# GSM_Power.net
KiCad netlist of a schematic drawn in Altium Designer
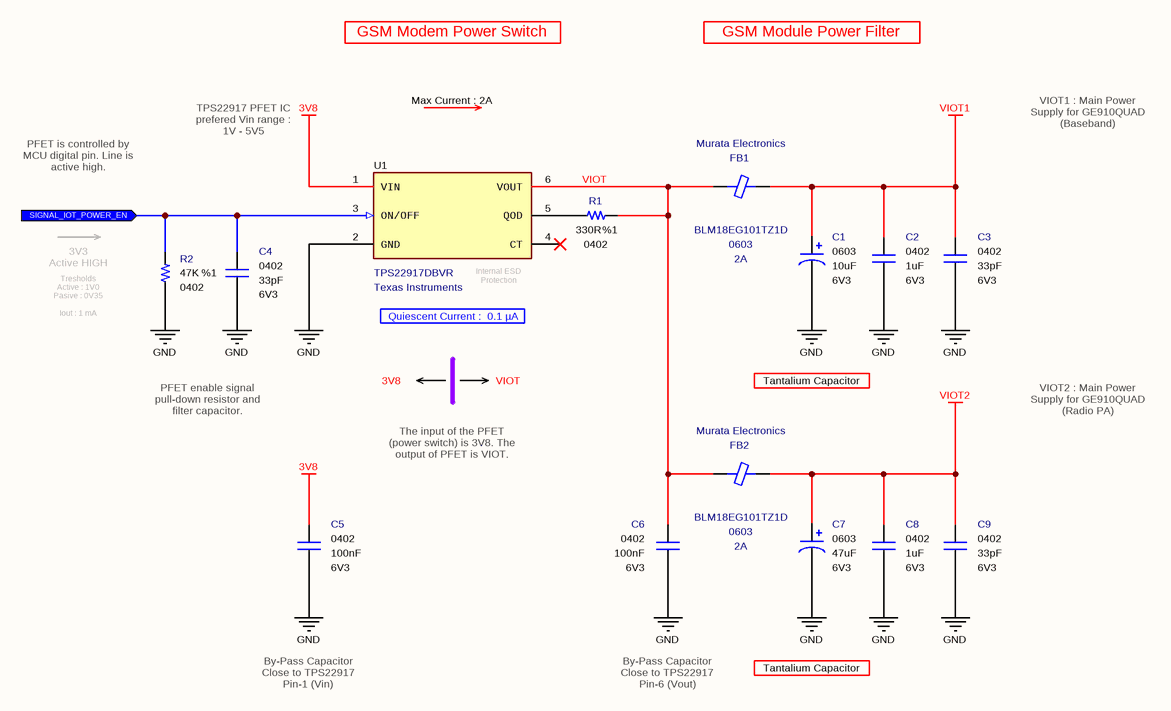
[diagram p0: GSM Power.SchDoc]

(export (version "E")
  (design (tool "Eeschema 10.0.6"))
  (components
    (comp (ref "C1")
      (value "10uF")
      (footprint "CAPACITOR_0603 - TANTALUM")
      (description "Capacitor - 10uF [0603] (Tantalium)")
      (fields
        (field (name "TOLERANCE") "20%")
        (field (name "CASE") "0603")
        (field (name "VOLTAGE") "6V3")
        (field (name "MANUFACTURER PART NUMBER") "F380J106MMAAH3")
      )
      (libsource (lib "Ovoo_Library") (part "Capacitor - 10uF [0603-6V3] (Tantalium)"))
    )
    (comp (ref "C2")
      (value "1uF")
      (footprint "CAPACITOR_0402")
      (description "Capacitor - 1uF [0402] (Ceramic)")
      (fields
        (field (name "TOLERANCE") "20%")
        (field (name "CASE") "0402")
        (field (name "VOLTAGE") "6V3")
        (field (name "MANUFACTURER PART NUMBER") "GRM153R60J105ME95D")
      )
      (libsource (lib "Ovoo_Library") (part "Capacitor - 1uF [0402-6V3]"))
    )
    (comp (ref "C3")
      (value "33pF")
      (footprint "CAPACITOR_0402")
      (description "Capacitor - 33pF [0402] (Ceramic)")
      (fields
        (field (name "TOLERANCE") "10%")
        (field (name "CASE") "0402")
        (field (name "VOLTAGE") "6V3")
        (field (name "MANUFACTURER PART NUMBER") "C0402C330J9RACAUTO")
      )
      (libsource (lib "Ovoo_Library") (part "Capacitor - 33pF [0402-6V3]"))
    )
    (comp (ref "C4")
      (value "33pF")
      (footprint "CAPACITOR_0402")
      (description "Capacitor - 33pF [0402] (Ceramic)")
      (fields
        (field (name "TOLERANCE") "10%")
        (field (name "CASE") "0402")
        (field (name "VOLTAGE") "6V3")
        (field (name "MANUFACTURER PART NUMBER") "C0402C330J9RACAUTO")
      )
      (libsource (lib "Ovoo_Library") (part "Capacitor - 33pF [0402-6V3]"))
    )
    (comp (ref "C5")
      (value "100nF")
      (footprint "CAPACITOR_0402")
      (description "Capacitor - 100nF [0402-6V3] (Ceramic)")
      (fields
        (field (name "CASE") "0402")
        (field (name "TOLERANCE") "%10")
        (field (name "VOLTAGE") "6V3")
        (field (name "MANUFACTURER PART NUMBER") "04026D104KAT4A")
      )
      (libsource (lib "Ovoo_Library") (part "Capacitor - 100nF [0402-6V3]"))
    )
    (comp (ref "C6")
      (value "100nF")
      (footprint "CAPACITOR_0402")
      (description "Capacitor - 100nF [0402-6V3] (Ceramic)")
      (fields
        (field (name "CASE") "0402")
        (field (name "TOLERANCE") "%10")
        (field (name "VOLTAGE") "6V3")
        (field (name "MANUFACTURER PART NUMBER") "04026D104KAT4A")
      )
      (libsource (lib "Ovoo_Library") (part "Capacitor - 100nF [0402-6V3]"))
    )
    (comp (ref "C7")
      (value "47uF")
      (footprint "CAPACITOR_0603 - TANTALUM")
      (description "Capacitor - 47uF [0603] (Tantalium)")
      (fields
        (field (name "TOLERANCE") "20%")
        (field (name "CASE") "0603")
        (field (name "VOLTAGE") "6V3")
        (field (name "MANUFACTURER PART NUMBER") "F380J476MMAAXEH3")
      )
      (libsource (lib "Ovoo_Library") (part "Capacitor - 47u [0603-6V3] (Tantalium)"))
    )
    (comp (ref "C8")
      (value "1uF")
      (footprint "CAPACITOR_0402")
      (description "Capacitor - 1uF [0402] (Ceramic)")
      (fields
        (field (name "TOLERANCE") "20%")
        (field (name "CASE") "0402")
        (field (name "VOLTAGE") "6V3")
        (field (name "MANUFACTURER PART NUMBER") "GRM153R60J105ME95D")
      )
      (libsource (lib "Ovoo_Library") (part "Capacitor - 1uF [0402-6V3]"))
    )
    (comp (ref "C9")
      (value "33pF")
      (footprint "CAPACITOR_0402")
      (description "Capacitor - 33pF [0402] (Ceramic)")
      (fields
        (field (name "TOLERANCE") "10%")
        (field (name "CASE") "0402")
        (field (name "VOLTAGE") "6V3")
        (field (name "MANUFACTURER PART NUMBER") "C0402C330J9RACAUTO")
      )
      (libsource (lib "Ovoo_Library") (part "Capacitor - 33pF [0402-6V3]"))
    )
    (comp (ref "FB1")
      (value "BLM18EG101TZ1D")
      (footprint "INDUCATOR_0603")
      (description "Ferrite Beads 0603 100ohms 2000mA Auto Infotainment")
      (fields
        (field (name "TOLERANCE") "25%")
        (field (name "CASE") "0603")
        (field (name "MAXIMUM DC CURRENT") "2A")
        (field (name "MOUSER PART NUMBER") "81-BLM18EG101TZ1D")
        (field (name "MANUFACTURER NAME") "Murata Electronics")
      )
      (libsource (lib "Ovoo_Library") (part "Ferrite Bead - 2A [0603]"))
    )
    (comp (ref "FB2")
      (value "BLM18EG101TZ1D")
      (footprint "INDUCATOR_0603")
      (description "Ferrite Beads 0603 100ohms 2000mA Auto Infotainment")
      (fields
        (field (name "TOLERANCE") "25%")
        (field (name "CASE") "0603")
        (field (name "MAXIMUM DC CURRENT") "2A")
        (field (name "MOUSER PART NUMBER") "81-BLM18EG101TZ1D")
        (field (name "MANUFACTURER NAME") "Murata Electronics")
      )
      (libsource (lib "Ovoo_Library") (part "Ferrite Bead - 2A [0603]"))
    )
    (comp (ref "R1")
      (value "330R")
      (footprint "RESISTOR_0402")
      (description "Thick Film Resistors - SMD 1/16 W 330 Ohm 1%")
      (fields
        (field (name "TOLERANCE") "%1")
        (field (name "CASE") "0402")
        (field (name "MANUFACTURER PART NUMBER") "CRCW0402330RFKED")
        (field (name "MOUSER PART NUMBER") "71-CRCW0402-330-E3")
      )
      (libsource (lib "Ovoo_Library") (part "Resistor - 330R"))
    )
    (comp (ref "R2")
      (value "47K")
      (footprint "RESISTOR_0402")
      (description "Thick Film Resistors - SMD 1/16 W 47 Kohms 1%")
      (fields
        (field (name "TOLERANCE") "%1")
        (field (name "CASE") "0402")
        (field (name "MANUFACTURER PART NUMBER") "CRCW040247K0FKED")
        (field (name "Comment") "47K - 0402 - %1 - 1/16W")
      )
      (libsource (lib "Ovoo_Library") (part "Resistor - 47K"))
    )
    (comp (ref "U1")
      (value "Power Switch")
      (footprint "SOT-23-6")
      (description "Power Switch MosFet")
      (fields
        (field (name "MOUSER PART NUMBER") "595-TPS22917DBVR")
        (field (name "MANUFACTURER PART NUMBER") "TPS22917DBVR")
        (field (name "MANUFACTURER NAME") "Texas Instruments")
      )
      (libsource (lib "Ovoo_Library") (part "IC - TPS22917DBVR"))
    )
  )
  (nets
    (net (code "1") (name "/SIGNAL_IOT_POWER_EN") (class "Default")
      (node (ref "C4") (pin "2") (pinfunction "2_2") (pintype "passive"))
      (node (ref "R2") (pin "2") (pinfunction "2_2") (pintype "passive"))
      (node (ref "U1") (pin "3") (pinfunction "ON/OFF_3") (pintype "input"))
    )
    (net (code "2") (name "/VIOT") (class "Default")
      (node (ref "C6") (pin "1") (pinfunction "1_1") (pintype "passive"))
      (node (ref "FB1") (pin "1") (pinfunction "1_1") (pintype "passive"))
      (node (ref "FB2") (pin "1") (pinfunction "1_1") (pintype "passive"))
      (node (ref "R1") (pin "1") (pinfunction "1_1") (pintype "passive"))
      (node (ref "U1") (pin "6") (pinfunction "VOUT_6") (pintype "power_in"))
    )
    (net (code "3") (name "3V8") (class "Default")
      (node (ref "C5") (pin "1") (pinfunction "1_1") (pintype "passive"))
      (node (ref "U1") (pin "1") (pinfunction "VIN_1") (pintype "power_in"))
    )
    (net (code "4") (name "GND") (class "Default")
      (node (ref "C1") (pin "2") (pinfunction "2_2") (pintype "passive"))
      (node (ref "C2") (pin "1") (pinfunction "1_1") (pintype "passive"))
      (node (ref "C3") (pin "1") (pinfunction "1_1") (pintype "passive"))
      (node (ref "C4") (pin "1") (pinfunction "1_1") (pintype "passive"))
      (node (ref "C5") (pin "2") (pinfunction "2_2") (pintype "passive"))
      (node (ref "C6") (pin "2") (pinfunction "2_2") (pintype "passive"))
      (node (ref "C7") (pin "2") (pinfunction "2_2") (pintype "passive"))
      (node (ref "C8") (pin "1") (pinfunction "1_1") (pintype "passive"))
      (node (ref "C9") (pin "1") (pinfunction "1_1") (pintype "passive"))
      (node (ref "R2") (pin "1") (pinfunction "1_1") (pintype "passive"))
      (node (ref "U1") (pin "2") (pinfunction "GND_2") (pintype "power_in"))
    )
    (net (code "5") (name "Net-(U1-QOD)") (class "Default")
      (node (ref "R1") (pin "2") (pinfunction "2_2") (pintype "passive"))
      (node (ref "U1") (pin "5") (pinfunction "QOD_5") (pintype "power_in"))
    )
    (net (code "6") (name "VIOT1") (class "Default")
      (node (ref "C1") (pin "1") (pinfunction "1_1") (pintype "passive"))
      (node (ref "C2") (pin "2") (pinfunction "2_2") (pintype "passive"))
      (node (ref "C3") (pin "2") (pinfunction "2_2") (pintype "passive"))
      (node (ref "FB1") (pin "2") (pinfunction "2_2") (pintype "passive"))
    )
    (net (code "7") (name "VIOT2") (class "Default")
      (node (ref "C7") (pin "1") (pinfunction "1_1") (pintype "passive"))
      (node (ref "C8") (pin "2") (pinfunction "2_2") (pintype "passive"))
      (node (ref "C9") (pin "2") (pinfunction "2_2") (pintype "passive"))
      (node (ref "FB2") (pin "2") (pinfunction "2_2") (pintype "passive"))
    )
    (net (code "8") (name "unconnected-(U1-CT-Pad4)") (class "Default")
      (node (ref "U1") (pin "4") (pinfunction "CT_4") (pintype "power_in+no_connect"))
    )
  )
)
